# AmbaSat-06-SI1132-A10-GMR.net
KiCad netlist of a schematic drawn in EAGLE
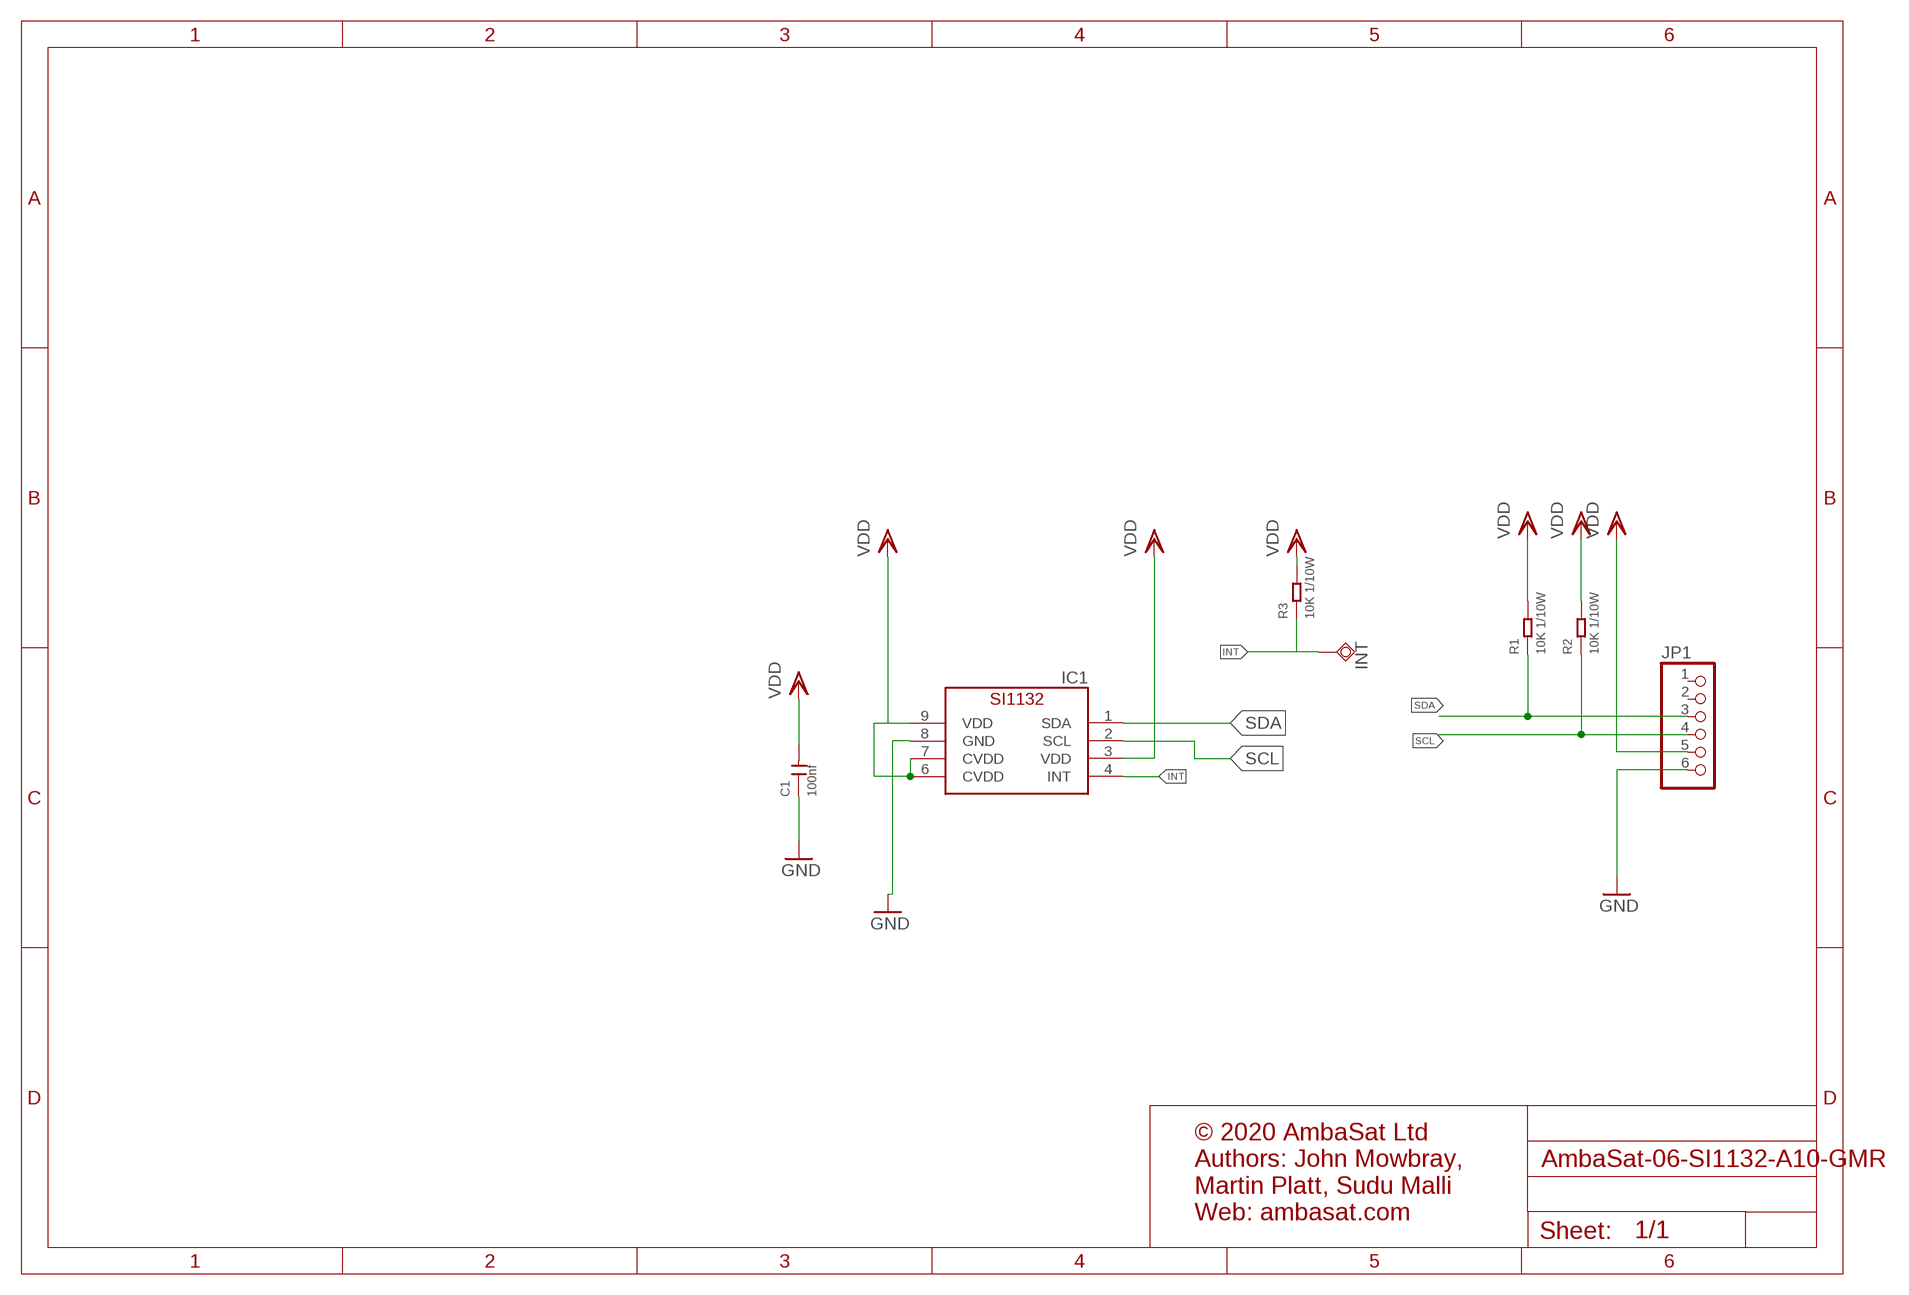
[diagram p0: schematic, sheet 1]

(export (version "E")
  (design (tool "Eeschema 10.0.6"))
  (components
    (comp (ref "C1")
      (value "100nf")
      (footprint "eagle-import:C0603")
      (fields (field (name "MPN") "CC0603KRX7R9BB104"))
      (libsource (lib "eagle-import") (part "CERAMIC-100NF-50V-10%-X7R(0603)"))
    )
    (comp (ref "IC1")
      (value "SL-SI1132")
      (footprint "eagle-import:SILICONLABS-SI1132")
      (libsource (lib "eagle-import") (part "SL-SI1132"))
    )
    (comp (ref "INT")
      (value "TESTPAD_TPSQTP12R")
      (footprint "eagle-import:TESTPAD_TP12R")
      (libsource (lib "eagle-import") (part "TESTPAD_TPSQTP12R"))
    )
    (comp (ref "JP1")
      (value "HEADER-1X6")
      (footprint "eagle-import:1X06_OVAL")
      (libsource (lib "eagle-import") (part "HEADER-1X6"))
    )
    (comp (ref "R1")
      (value "10K 1/10W")
      (footprint "eagle-import:R0603")
      (fields (field (name "MPN") "RC0603JR-0710KL"))
      (libsource (lib "eagle-import") (part "SMD-RES-10K-5%-1/10W(0603)"))
    )
    (comp (ref "R2")
      (value "10K 1/10W")
      (footprint "eagle-import:R0603")
      (fields (field (name "MPN") "RC0603JR-0710KL"))
      (libsource (lib "eagle-import") (part "SMD-RES-10K-5%-1/10W(0603)"))
    )
    (comp (ref "R3")
      (value "10K 1/10W")
      (footprint "eagle-import:R0603")
      (fields (field (name "MPN") "RC0603JR-0710KL"))
      (libsource (lib "eagle-import") (part "SMD-RES-10K-5%-1/10W(0603)"))
    )
  )
  (nets
    (net (code "1") (name "GND") (class "Default")
      (node (ref "C1") (pin "1") (pinfunction "1_1") (pintype "passive"))
      (node (ref "IC1") (pin "8") (pinfunction "GND_8") (pintype "bidirectional"))
      (node (ref "JP1") (pin "6") (pinfunction "6_6") (pintype "passive"))
    )
    (net (code "2") (name "INT") (class "Default")
      (node (ref "IC1") (pin "4") (pinfunction "INT_4") (pintype "bidirectional"))
      (node (ref "INT") (pin "TP") (pinfunction "TP_TP") (pintype "input"))
      (node (ref "R3") (pin "1") (pinfunction "1_1") (pintype "passive"))
    )
    (net (code "3") (name "SCL") (class "Default")
      (node (ref "IC1") (pin "2") (pinfunction "SCL_2") (pintype "bidirectional"))
      (node (ref "JP1") (pin "4") (pinfunction "4_4") (pintype "passive"))
      (node (ref "R2") (pin "1") (pinfunction "1_1") (pintype "passive"))
    )
    (net (code "4") (name "SDA") (class "Default")
      (node (ref "IC1") (pin "1") (pinfunction "SDA_1") (pintype "bidirectional"))
      (node (ref "JP1") (pin "3") (pinfunction "3_3") (pintype "passive"))
      (node (ref "R1") (pin "1") (pinfunction "1_1") (pintype "passive"))
    )
    (net (code "5") (name "VDD") (class "Default")
      (node (ref "C1") (pin "2") (pinfunction "2_2") (pintype "passive"))
      (node (ref "IC1") (pin "3") (pinfunction "VDD_3") (pintype "bidirectional"))
      (node (ref "IC1") (pin "6") (pinfunction "CVDD_6") (pintype "bidirectional"))
      (node (ref "IC1") (pin "7") (pinfunction "CVDD_7") (pintype "bidirectional"))
      (node (ref "IC1") (pin "9") (pinfunction "VDD_9") (pintype "bidirectional"))
      (node (ref "JP1") (pin "5") (pinfunction "5_5") (pintype "passive"))
      (node (ref "R1") (pin "2") (pinfunction "2_2") (pintype "passive"))
      (node (ref "R2") (pin "2") (pinfunction "2_2") (pintype "passive"))
      (node (ref "R3") (pin "2") (pinfunction "2_2") (pintype "passive"))
    )
    (net (code "6") (name "unconnected-(JP1-Pad1)") (class "Default")
      (node (ref "JP1") (pin "1") (pinfunction "1_1") (pintype "passive"))
    )
    (net (code "7") (name "unconnected-(JP1-Pad2)") (class "Default")
      (node (ref "JP1") (pin "2") (pinfunction "2_2") (pintype "passive"))
    )
  )
)
